# V2.net
KiCad netlist of a schematic drawn in Altium Designer
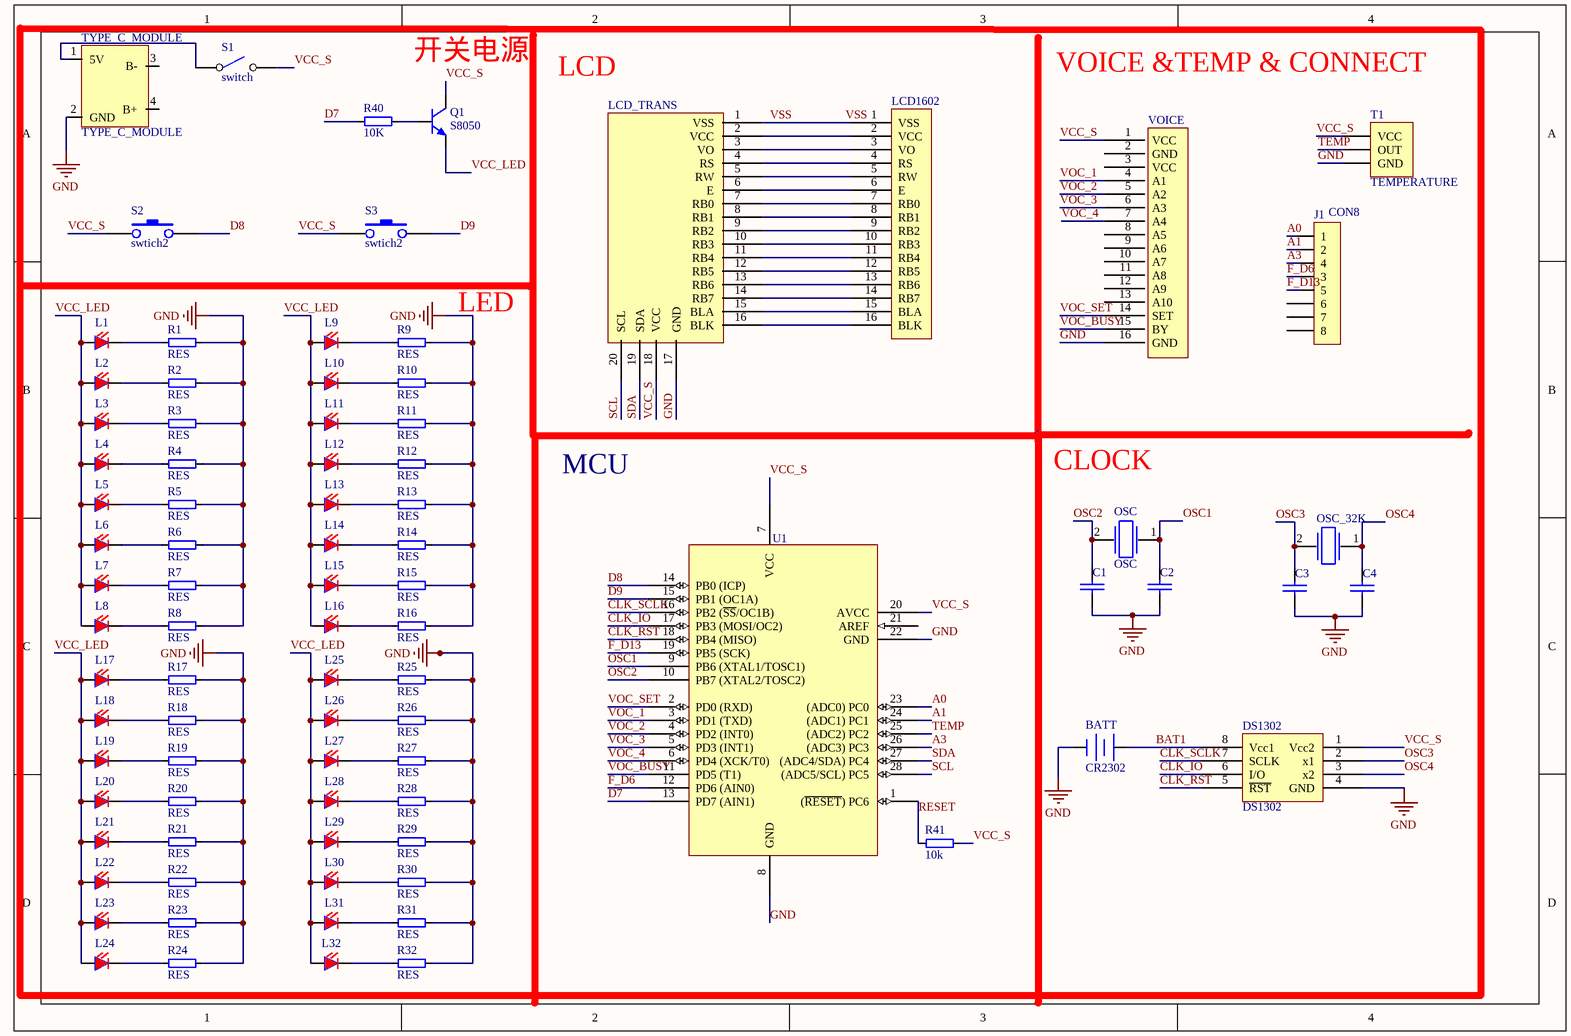
[diagram p0: 生日礼物V2.SchDoc]

(export (version "E")
  (design (tool "Eeschema 10.0.6"))
  (components
    (comp (ref "BATT")
      (value "CR2302")
      (footprint "CR2032_C")
      (description "Multicell Battery")
      (fields (field (name "PUBLISHER") "Altium Limited"))
      (libsource (lib "最小系统") (part "BATTERY"))
    )
    (comp (ref "C1") (value "~") (footprint "CAP") (libsource (lib "最小系统") (part "CAP")))
    (comp (ref "C2") (value "~") (footprint "CAP") (libsource (lib "最小系统") (part "CAP")))
    (comp (ref "C3") (value "~") (footprint "CAP") (libsource (lib "最小系统") (part "CAP")))
    (comp (ref "C4") (value "~") (footprint "CAP") (libsource (lib "最小系统") (part "CAP")))
    (comp (ref "DS1302") (value "DS1302") (footprint "DS1302") (libsource (lib "最小系统") (part "DS1302")))
    (comp (ref "J1") (value "CON8") (footprint "CON8") (libsource (lib "最小系统") (part "CON8")))
    (comp (ref "L1") (value "~") (footprint "LED 5MM-Y") (libsource (lib "最小系统") (part "LED")))
    (comp (ref "L2") (value "~") (footprint "LED 5MM-Y") (libsource (lib "最小系统") (part "LED")))
    (comp (ref "L3") (value "~") (footprint "LED 5MM-Y") (libsource (lib "最小系统") (part "LED")))
    (comp (ref "L4") (value "~") (footprint "LED 5MM-Y") (libsource (lib "最小系统") (part "LED")))
    (comp (ref "L5") (value "~") (footprint "LED 5MM-Y") (libsource (lib "最小系统") (part "LED")))
    (comp (ref "L6") (value "~") (footprint "LED 5MM-Y") (libsource (lib "最小系统") (part "LED")))
    (comp (ref "L7") (value "~") (footprint "LED 5MM-Y") (libsource (lib "最小系统") (part "LED")))
    (comp (ref "L8") (value "~") (footprint "LED 5MM-Y") (libsource (lib "最小系统") (part "LED")))
    (comp (ref "L9") (value "~") (footprint "LED 5MM-Y") (libsource (lib "最小系统") (part "LED")))
    (comp (ref "L10") (value "~") (footprint "LED 5MM-Y") (libsource (lib "最小系统") (part "LED")))
    (comp (ref "L11") (value "~") (footprint "LED 5MM-Y") (libsource (lib "最小系统") (part "LED")))
    (comp (ref "L12") (value "~") (footprint "LED 5MM-Y") (libsource (lib "最小系统") (part "LED")))
    (comp (ref "L13") (value "~") (footprint "LED 5MM-Y") (libsource (lib "最小系统") (part "LED")))
    (comp (ref "L14") (value "~") (footprint "LED 5MM-Y") (libsource (lib "最小系统") (part "LED")))
    (comp (ref "L15") (value "~") (footprint "LED 5MM-Y") (libsource (lib "最小系统") (part "LED")))
    (comp (ref "L16") (value "~") (footprint "LED 5MM-Y") (libsource (lib "最小系统") (part "LED")))
    (comp (ref "L17") (value "~") (footprint "LED 5MM-Y") (libsource (lib "最小系统") (part "LED")))
    (comp (ref "L18") (value "~") (footprint "LED 5MM-Y") (libsource (lib "最小系统") (part "LED")))
    (comp (ref "L19") (value "~") (footprint "LED 5MM-Y") (libsource (lib "最小系统") (part "LED")))
    (comp (ref "L20") (value "~") (footprint "LED 5MM-Y") (libsource (lib "最小系统") (part "LED")))
    (comp (ref "L21") (value "~") (footprint "LED 5MM-Y") (libsource (lib "最小系统") (part "LED")))
    (comp (ref "L22") (value "~") (footprint "LED 5MM-Y") (libsource (lib "最小系统") (part "LED")))
    (comp (ref "L23") (value "~") (footprint "LED 5MM-Y") (libsource (lib "最小系统") (part "LED")))
    (comp (ref "L24") (value "~") (footprint "LED 5MM-Y") (libsource (lib "最小系统") (part "LED")))
    (comp (ref "L25") (value "~") (footprint "LED 5MM-Y") (libsource (lib "最小系统") (part "LED")))
    (comp (ref "L26") (value "~") (footprint "LED 5MM-Y") (libsource (lib "最小系统") (part "LED")))
    (comp (ref "L27") (value "~") (footprint "LED 5MM-Y") (libsource (lib "最小系统") (part "LED")))
    (comp (ref "L28") (value "~") (footprint "LED 5MM-Y") (libsource (lib "最小系统") (part "LED")))
    (comp (ref "L29") (value "~") (footprint "LED 5MM-Y") (libsource (lib "最小系统") (part "LED")))
    (comp (ref "L30") (value "~") (footprint "LED 5MM-Y") (libsource (lib "最小系统") (part "LED")))
    (comp (ref "L31") (value "~") (footprint "LED 5MM-Y") (libsource (lib "最小系统") (part "LED")))
    (comp (ref "L32") (value "~") (footprint "LED 5MM-Y") (libsource (lib "最小系统") (part "LED")))
    (comp (ref "LCD1602") (value "~") (footprint "LCD1602") (libsource (lib "最小系统") (part "LCD1602")))
    (comp (ref "LCD_TRANS") (value "~") (footprint "LCD-TRANS") (libsource (lib "最小系统") (part "LCD_TRANS")))
    (comp (ref "OSC")
      (value "OSC")
      (footprint "OSC HC-49U")
      (description "晶振 32.768KHZ")
      (libsource (lib "最小系统") (part "OSC"))
    )
    (comp (ref "OSC_32K") (value "~") (footprint "osc_32.768K") (libsource (lib "生日礼物V2") (part "OSC_32K")))
    (comp (ref "Q1")
      (value "S8050")
      (footprint "TO92")
      (description "高频放大-NPN型")
      (fields (field (name "版权归属") "源创客"))
      (libsource (lib "最小系统") (part "8050-DIP"))
    )
    (comp (ref "R1") (value "RES") (footprint "0805R") (libsource (lib "最小系统") (part "RES")))
    (comp (ref "R2") (value "RES") (footprint "0805R") (libsource (lib "最小系统") (part "RES")))
    (comp (ref "R3") (value "RES") (footprint "0805R") (libsource (lib "最小系统") (part "RES")))
    (comp (ref "R4") (value "RES") (footprint "0805R") (libsource (lib "最小系统") (part "RES")))
    (comp (ref "R5") (value "RES") (footprint "0805R") (libsource (lib "最小系统") (part "RES")))
    (comp (ref "R6") (value "RES") (footprint "0805R") (libsource (lib "最小系统") (part "RES")))
    (comp (ref "R7") (value "RES") (footprint "0805R") (libsource (lib "最小系统") (part "RES")))
    (comp (ref "R8") (value "RES") (footprint "0805R") (libsource (lib "最小系统") (part "RES")))
    (comp (ref "R9") (value "RES") (footprint "0805R") (libsource (lib "最小系统") (part "RES")))
    (comp (ref "R10") (value "RES") (footprint "0805R") (libsource (lib "最小系统") (part "RES")))
    (comp (ref "R11") (value "RES") (footprint "0805R") (libsource (lib "最小系统") (part "RES")))
    (comp (ref "R12") (value "RES") (footprint "0805R") (libsource (lib "最小系统") (part "RES")))
    (comp (ref "R13") (value "RES") (footprint "0805R") (libsource (lib "最小系统") (part "RES")))
    (comp (ref "R14") (value "RES") (footprint "0805R") (libsource (lib "最小系统") (part "RES")))
    (comp (ref "R15") (value "RES") (footprint "0805R") (libsource (lib "最小系统") (part "RES")))
    (comp (ref "R16") (value "RES") (footprint "0805R") (libsource (lib "最小系统") (part "RES")))
    (comp (ref "R17") (value "RES") (footprint "0805R") (libsource (lib "最小系统") (part "RES")))
    (comp (ref "R18") (value "RES") (footprint "0805R") (libsource (lib "最小系统") (part "RES")))
    (comp (ref "R19") (value "RES") (footprint "0805R") (libsource (lib "最小系统") (part "RES")))
    (comp (ref "R20") (value "RES") (footprint "0805R") (libsource (lib "最小系统") (part "RES")))
    (comp (ref "R21") (value "RES") (footprint "0805R") (libsource (lib "最小系统") (part "RES")))
    (comp (ref "R22") (value "RES") (footprint "0805R") (libsource (lib "最小系统") (part "RES")))
    (comp (ref "R23") (value "RES") (footprint "0805R") (libsource (lib "最小系统") (part "RES")))
    (comp (ref "R24") (value "RES") (footprint "0805R") (libsource (lib "最小系统") (part "RES")))
    (comp (ref "R25") (value "RES") (footprint "0805R") (libsource (lib "最小系统") (part "RES")))
    (comp (ref "R26") (value "RES") (footprint "0805R") (libsource (lib "最小系统") (part "RES")))
    (comp (ref "R27") (value "RES") (footprint "0805R") (libsource (lib "最小系统") (part "RES")))
    (comp (ref "R28") (value "RES") (footprint "0805R") (libsource (lib "最小系统") (part "RES")))
    (comp (ref "R29") (value "RES") (footprint "0805R") (libsource (lib "最小系统") (part "RES")))
    (comp (ref "R30") (value "RES") (footprint "0805R") (libsource (lib "最小系统") (part "RES")))
    (comp (ref "R31") (value "RES") (footprint "0805R") (libsource (lib "最小系统") (part "RES")))
    (comp (ref "R32") (value "RES") (footprint "0805R") (libsource (lib "最小系统") (part "RES")))
    (comp (ref "R40") (value "10K") (footprint "0805R") (libsource (lib "最小系统") (part "RES")))
    (comp (ref "R41") (value "10k") (footprint "0805R") (libsource (lib "最小系统") (part "RES")))
    (comp (ref "S1")
      (value "switch")
      (footprint "switch")
      (description "主开关")
      (libsource (lib "最小系统") (part "switch"))
    )
    (comp (ref "S2")
      (value "swtich2")
      (footprint "switch")
      (description "按钮触发")
      (libsource (lib "最小系统") (part "swtich"))
    )
    (comp (ref "S3") (value "swtich2") (footprint "switch") (libsource (lib "最小系统") (part "swtich")))
    (comp (ref "T1")
      (value "TEMPERATURE")
      (footprint "TEMP_SENSOR")
      (description "温度传感器")
      (libsource (lib "最小系统") (part "TEMPERATURE"))
    )
    (comp (ref "TYPE_C_MODULE")
      (value "TYPE_C_MODULE")
      (footprint "TYPE_C_Module")
      (libsource (lib "最小系统") (part "TYPE_C_MODULE"))
    )
    (comp (ref "U1")
      (value "~")
      (footprint "DIP28")
      (description "Atmel Microcontroller - Library created by carel..  <www.mpfreezone.com>")
      (libsource (lib "最小系统") (part "ATMEGA8_DIP28"))
    )
    (comp (ref "VOICE") (value "~") (footprint "VOICE") (libsource (lib "最小系统") (part "VOICE")))
  )
  (nets
    (net (code "1") (name "/A0") (class "Default")
      (node (ref "J1") (pin "1") (pinfunction "1_1") (pintype "passive"))
      (node (ref "U1") (pin "23") (pinfunction "(ADC0)_PC0_23") (pintype "bidirectional"))
    )
    (net (code "2") (name "/A1") (class "Default")
      (node (ref "J1") (pin "2") (pinfunction "2_2") (pintype "passive"))
      (node (ref "U1") (pin "24") (pinfunction "(ADC1)_PC1_24") (pintype "bidirectional"))
    )
    (net (code "3") (name "/A3") (class "Default")
      (node (ref "J1") (pin "4") (pinfunction "4_4") (pintype "passive"))
      (node (ref "U1") (pin "26") (pinfunction "(ADC3)_PC3_26") (pintype "bidirectional"))
    )
    (net (code "4") (name "/BAT1") (class "Default")
      (node (ref "BATT") (pin "1") (pinfunction "+_1") (pintype "passive"))
      (node (ref "DS1302") (pin "8") (pinfunction "Vcc1_8") (pintype "passive"))
    )
    (net (code "5") (name "/CLK_IO") (class "Default")
      (node (ref "DS1302") (pin "6") (pinfunction "I/O_6") (pintype "passive"))
      (node (ref "U1") (pin "17") (pinfunction "PB3_(MOSI/OC2)_17") (pintype "bidirectional"))
    )
    (net (code "6") (name "/CLK_RST") (class "Default")
      (node (ref "DS1302") (pin "5") (pinfunction "~{RST}_5") (pintype "passive"))
      (node (ref "U1") (pin "18") (pinfunction "PB4_(MISO)_18") (pintype "bidirectional"))
    )
    (net (code "7") (name "/CLK_SCLK") (class "Default")
      (node (ref "DS1302") (pin "7") (pinfunction "SCLK_7") (pintype "passive"))
      (node (ref "U1") (pin "16") (pinfunction "PB2_(~{SS}/OC1B)_16") (pintype "bidirectional"))
    )
    (net (code "8") (name "/D7") (class "Default")
      (node (ref "R40") (pin "1") (pinfunction "1_1") (pintype "passive"))
      (node (ref "U1") (pin "13") (pinfunction "PD7_(AIN1)_13") (pintype "passive"))
    )
    (net (code "9") (name "/D8") (class "Default")
      (node (ref "S2") (pin "2") (pinfunction "2_2") (pintype "passive"))
      (node (ref "U1") (pin "14") (pinfunction "PB0_(ICP)_14") (pintype "bidirectional"))
    )
    (net (code "10") (name "/D9") (class "Default")
      (node (ref "S3") (pin "2") (pinfunction "2_2") (pintype "passive"))
      (node (ref "U1") (pin "15") (pinfunction "PB1_(OC1A)_15") (pintype "bidirectional"))
    )
    (net (code "11") (name "/F_D6") (class "Default")
      (node (ref "J1") (pin "3") (pinfunction "3_3") (pintype "passive"))
      (node (ref "U1") (pin "12") (pinfunction "PD6_(AIN0)_12") (pintype "passive"))
    )
    (net (code "12") (name "/F_D13") (class "Default")
      (node (ref "J1") (pin "5") (pinfunction "5_5") (pintype "passive"))
      (node (ref "U1") (pin "19") (pinfunction "PB5_(SCK)_19") (pintype "bidirectional"))
    )
    (net (code "13") (name "/OSC1") (class "Default")
      (node (ref "C2") (pin "1") (pinfunction "1_1") (pintype "passive"))
      (node (ref "OSC") (pin "1") (pintype "passive"))
      (node (ref "U1") (pin "9") (pinfunction "PB6_(XTAL1/TOSC1)_9") (pintype "passive"))
    )
    (net (code "14") (name "/OSC2") (class "Default")
      (node (ref "C1") (pin "1") (pinfunction "1_1") (pintype "passive"))
      (node (ref "OSC") (pin "2") (pintype "passive"))
      (node (ref "U1") (pin "10") (pinfunction "PB7_(XTAL2/TOSC2)_10") (pintype "passive"))
    )
    (net (code "15") (name "/OSC3") (class "Default")
      (node (ref "C3") (pin "1") (pinfunction "1_1") (pintype "passive"))
      (node (ref "DS1302") (pin "2") (pinfunction "x1_2") (pintype "passive"))
      (node (ref "OSC_32K") (pin "2") (pintype "passive"))
    )
    (net (code "16") (name "/OSC4") (class "Default")
      (node (ref "C4") (pin "1") (pinfunction "1_1") (pintype "passive"))
      (node (ref "DS1302") (pin "3") (pinfunction "x2_3") (pintype "passive"))
      (node (ref "OSC_32K") (pin "1") (pintype "passive"))
    )
    (net (code "17") (name "/RESET") (class "Default")
      (node (ref "R41") (pin "1") (pinfunction "1_1") (pintype "passive"))
      (node (ref "U1") (pin "1") (pinfunction "(~{RESET})_PC6_1") (pintype "bidirectional"))
    )
    (net (code "18") (name "/SCL") (class "Default")
      (node (ref "LCD_TRANS") (pin "20") (pinfunction "SCL_20") (pintype "passive"))
      (node (ref "U1") (pin "28") (pinfunction "(ADC5/SCL)_PC5_28") (pintype "bidirectional"))
    )
    (net (code "19") (name "/SDA") (class "Default")
      (node (ref "LCD_TRANS") (pin "19") (pinfunction "SDA_19") (pintype "passive"))
      (node (ref "U1") (pin "27") (pinfunction "(ADC4/SDA)_PC4_27") (pintype "bidirectional"))
    )
    (net (code "20") (name "/TEMP") (class "Default")
      (node (ref "T1") (pin "2") (pinfunction "OUT_2") (pintype "passive"))
      (node (ref "U1") (pin "25") (pinfunction "(ADC2)_PC2_25") (pintype "bidirectional"))
    )
    (net (code "21") (name "/VCC_LED") (class "Default")
      (node (ref "L1") (pin "1") (pinfunction "A_1") (pintype "passive"))
      (node (ref "L10") (pin "1") (pinfunction "A_1") (pintype "passive"))
      (node (ref "L11") (pin "1") (pinfunction "A_1") (pintype "passive"))
      (node (ref "L12") (pin "1") (pinfunction "A_1") (pintype "passive"))
      (node (ref "L13") (pin "1") (pinfunction "A_1") (pintype "passive"))
      (node (ref "L14") (pin "1") (pinfunction "A_1") (pintype "passive"))
      (node (ref "L15") (pin "1") (pinfunction "A_1") (pintype "passive"))
      (node (ref "L16") (pin "1") (pinfunction "A_1") (pintype "passive"))
      (node (ref "L17") (pin "1") (pinfunction "A_1") (pintype "passive"))
      (node (ref "L18") (pin "1") (pinfunction "A_1") (pintype "passive"))
      (node (ref "L19") (pin "1") (pinfunction "A_1") (pintype "passive"))
      (node (ref "L2") (pin "1") (pinfunction "A_1") (pintype "passive"))
      (node (ref "L20") (pin "1") (pinfunction "A_1") (pintype "passive"))
      (node (ref "L21") (pin "1") (pinfunction "A_1") (pintype "passive"))
      (node (ref "L22") (pin "1") (pinfunction "A_1") (pintype "passive"))
      (node (ref "L23") (pin "1") (pinfunction "A_1") (pintype "passive"))
      (node (ref "L24") (pin "1") (pinfunction "A_1") (pintype "passive"))
      (node (ref "L25") (pin "1") (pinfunction "A_1") (pintype "passive"))
      (node (ref "L26") (pin "1") (pinfunction "A_1") (pintype "passive"))
      (node (ref "L27") (pin "1") (pinfunction "A_1") (pintype "passive"))
      (node (ref "L28") (pin "1") (pinfunction "A_1") (pintype "passive"))
      (node (ref "L29") (pin "1") (pinfunction "A_1") (pintype "passive"))
      (node (ref "L3") (pin "1") (pinfunction "A_1") (pintype "passive"))
      (node (ref "L30") (pin "1") (pinfunction "A_1") (pintype "passive"))
      (node (ref "L31") (pin "1") (pinfunction "A_1") (pintype "passive"))
      (node (ref "L32") (pin "1") (pinfunction "A_1") (pintype "passive"))
      (node (ref "L4") (pin "1") (pinfunction "A_1") (pintype "passive"))
      (node (ref "L5") (pin "1") (pinfunction "A_1") (pintype "passive"))
      (node (ref "L6") (pin "1") (pinfunction "A_1") (pintype "passive"))
      (node (ref "L7") (pin "1") (pinfunction "A_1") (pintype "passive"))
      (node (ref "L8") (pin "1") (pinfunction "A_1") (pintype "passive"))
      (node (ref "L9") (pin "1") (pinfunction "A_1") (pintype "passive"))
      (node (ref "Q1") (pin "1") (pinfunction "E_1") (pintype "passive"))
    )
    (net (code "22") (name "/VCC_S") (class "Default")
      (node (ref "DS1302") (pin "1") (pinfunction "Vcc2_1") (pintype "passive"))
      (node (ref "LCD_TRANS") (pin "18") (pinfunction "VCC_18") (pintype "passive"))
      (node (ref "Q1") (pin "3") (pinfunction "C_3") (pintype "passive"))
      (node (ref "R41") (pin "2") (pinfunction "2_2") (pintype "passive"))
      (node (ref "S1") (pin "2") (pinfunction "2_2") (pintype "passive"))
      (node (ref "S2") (pin "1") (pinfunction "1_1") (pintype "passive"))
      (node (ref "S3") (pin "1") (pinfunction "1_1") (pintype "passive"))
      (node (ref "T1") (pin "1") (pinfunction "VCC_1") (pintype "passive"))
      (node (ref "U1") (pin "20") (pinfunction "AVCC_20") (pintype "passive"))
      (node (ref "U1") (pin "7") (pinfunction "VCC_7") (pintype "passive"))
      (node (ref "VOICE") (pin "1") (pinfunction "VCC_1") (pintype "passive"))
    )
    (net (code "23") (name "/VOC_1") (class "Default")
      (node (ref "U1") (pin "3") (pinfunction "PD1_(TXD)_3") (pintype "bidirectional"))
      (node (ref "VOICE") (pin "4") (pinfunction "A1_4") (pintype "passive"))
    )
    (net (code "24") (name "/VOC_2") (class "Default")
      (node (ref "U1") (pin "4") (pinfunction "PD2_(INT0)_4") (pintype "bidirectional"))
      (node (ref "VOICE") (pin "5") (pinfunction "A2_5") (pintype "passive"))
    )
    (net (code "25") (name "/VOC_3") (class "Default")
      (node (ref "U1") (pin "5") (pinfunction "PD3_(INT1)_5") (pintype "bidirectional"))
      (node (ref "VOICE") (pin "6") (pinfunction "A3_6") (pintype "passive"))
    )
    (net (code "26") (name "/VOC_4") (class "Default")
      (node (ref "U1") (pin "6") (pinfunction "PD4_(XCK/T0)_6") (pintype "bidirectional"))
      (node (ref "VOICE") (pin "7") (pinfunction "A4_7") (pintype "passive"))
    )
    (net (code "27") (name "/VOC_BUSY") (class "Default")
      (node (ref "U1") (pin "11") (pinfunction "PD5_(T1)_11") (pintype "passive"))
      (node (ref "VOICE") (pin "15") (pinfunction "BY_15") (pintype "passive"))
    )
    (net (code "28") (name "/VOC_SET") (class "Default")
      (node (ref "U1") (pin "2") (pinfunction "PD0_(RXD)_2") (pintype "bidirectional"))
      (node (ref "VOICE") (pin "14") (pinfunction "SET_14") (pintype "passive"))
    )
    (net (code "29") (name "/VSS") (class "Default")
      (node (ref "LCD1602") (pin "1") (pinfunction "VSS_1") (pintype "passive"))
      (node (ref "LCD_TRANS") (pin "1") (pinfunction "VSS_1") (pintype "passive"))
    )
    (net (code "30") (name "GND") (class "Default")
      (node (ref "BATT") (pin "2") (pinfunction "-_2") (pintype "passive"))
      (node (ref "C1") (pin "2") (pinfunction "2_2") (pintype "passive"))
      (node (ref "C2") (pin "2") (pinfunction "2_2") (pintype "passive"))
      (node (ref "C3") (pin "2") (pinfunction "2_2") (pintype "passive"))
      (node (ref "C4") (pin "2") (pinfunction "2_2") (pintype "passive"))
      (node (ref "DS1302") (pin "4") (pinfunction "GND_4") (pintype "passive"))
      (node (ref "LCD_TRANS") (pin "17") (pinfunction "GND_17") (pintype "passive"))
      (node (ref "R1") (pin "2") (pinfunction "2_2") (pintype "passive"))
      (node (ref "R10") (pin "2") (pinfunction "2_2") (pintype "passive"))
      (node (ref "R11") (pin "2") (pinfunction "2_2") (pintype "passive"))
      (node (ref "R12") (pin "2") (pinfunction "2_2") (pintype "passive"))
      (node (ref "R13") (pin "2") (pinfunction "2_2") (pintype "passive"))
      (node (ref "R14") (pin "2") (pinfunction "2_2") (pintype "passive"))
      (node (ref "R15") (pin "2") (pinfunction "2_2") (pintype "passive"))
      (node (ref "R16") (pin "2") (pinfunction "2_2") (pintype "passive"))
      (node (ref "R17") (pin "2") (pinfunction "2_2") (pintype "passive"))
      (node (ref "R18") (pin "2") (pinfunction "2_2") (pintype "passive"))
      (node (ref "R19") (pin "2") (pinfunction "2_2") (pintype "passive"))
      (node (ref "R2") (pin "2") (pinfunction "2_2") (pintype "passive"))
      (node (ref "R20") (pin "2") (pinfunction "2_2") (pintype "passive"))
      (node (ref "R21") (pin "2") (pinfunction "2_2") (pintype "passive"))
      (node (ref "R22") (pin "2") (pinfunction "2_2") (pintype "passive"))
      (node (ref "R23") (pin "2") (pinfunction "2_2") (pintype "passive"))
      (node (ref "R24") (pin "2") (pinfunction "2_2") (pintype "passive"))
      (node (ref "R25") (pin "2") (pinfunction "2_2") (pintype "passive"))
      (node (ref "R26") (pin "2") (pinfunction "2_2") (pintype "passive"))
      (node (ref "R27") (pin "2") (pinfunction "2_2") (pintype "passive"))
      (node (ref "R28") (pin "2") (pinfunction "2_2") (pintype "passive"))
      (node (ref "R29") (pin "2") (pinfunction "2_2") (pintype "passive"))
      (node (ref "R3") (pin "2") (pinfunction "2_2") (pintype "passive"))
      (node (ref "R30") (pin "2") (pinfunction "2_2") (pintype "passive"))
      (node (ref "R31") (pin "2") (pinfunction "2_2") (pintype "passive"))
      (node (ref "R32") (pin "2") (pinfunction "2_2") (pintype "passive"))
      (node (ref "R4") (pin "2") (pinfunction "2_2") (pintype "passive"))
      (node (ref "R5") (pin "2") (pinfunction "2_2") (pintype "passive"))
      (node (ref "R6") (pin "2") (pinfunction "2_2") (pintype "passive"))
      (node (ref "R7") (pin "2") (pinfunction "2_2") (pintype "passive"))
      (node (ref "R8") (pin "2") (pinfunction "2_2") (pintype "passive"))
      (node (ref "R9") (pin "2") (pinfunction "2_2") (pintype "passive"))
      (node (ref "T1") (pin "3") (pinfunction "GND_3") (pintype "passive"))
      (node (ref "TYPE_C_MODULE") (pin "2") (pinfunction "GND_2") (pintype "passive"))
      (node (ref "U1") (pin "22") (pinfunction "GND_22") (pintype "passive"))
      (node (ref "U1") (pin "8") (pinfunction "GND_8") (pintype "passive"))
      (node (ref "VOICE") (pin "16") (pinfunction "GND_16") (pintype "passive"))
    )
    (net (code "31") (name "Net-(L1-K)") (class "Default")
      (node (ref "L1") (pin "2") (pinfunction "K_2") (pintype "passive"))
      (node (ref "R1") (pin "1") (pinfunction "1_1") (pintype "passive"))
    )
    (net (code "32") (name "Net-(L2-K)") (class "Default")
      (node (ref "L2") (pin "2") (pinfunction "K_2") (pintype "passive"))
      (node (ref "R2") (pin "1") (pinfunction "1_1") (pintype "passive"))
    )
    (net (code "33") (name "Net-(L3-K)") (class "Default")
      (node (ref "L3") (pin "2") (pinfunction "K_2") (pintype "passive"))
      (node (ref "R3") (pin "1") (pinfunction "1_1") (pintype "passive"))
    )
    (net (code "34") (name "Net-(L4-K)") (class "Default")
      (node (ref "L4") (pin "2") (pinfunction "K_2") (pintype "passive"))
      (node (ref "R4") (pin "1") (pinfunction "1_1") (pintype "passive"))
    )
    (net (code "35") (name "Net-(L5-K)") (class "Default")
      (node (ref "L5") (pin "2") (pinfunction "K_2") (pintype "passive"))
      (node (ref "R5") (pin "1") (pinfunction "1_1") (pintype "passive"))
    )
    (net (code "36") (name "Net-(L6-K)") (class "Default")
      (node (ref "L6") (pin "2") (pinfunction "K_2") (pintype "passive"))
      (node (ref "R6") (pin "1") (pinfunction "1_1") (pintype "passive"))
    )
    (net (code "37") (name "Net-(L7-K)") (class "Default")
      (node (ref "L7") (pin "2") (pinfunction "K_2") (pintype "passive"))
      (node (ref "R7") (pin "1") (pinfunction "1_1") (pintype "passive"))
    )
    (net (code "38") (name "Net-(L8-K)") (class "Default")
      (node (ref "L8") (pin "2") (pinfunction "K_2") (pintype "passive"))
      (node (ref "R8") (pin "1") (pinfunction "1_1") (pintype "passive"))
    )
    (net (code "39") (name "Net-(L9-K)") (class "Default")
      (node (ref "L9") (pin "2") (pinfunction "K_2") (pintype "passive"))
      (node (ref "R9") (pin "1") (pinfunction "1_1") (pintype "passive"))
    )
    (net (code "40") (name "Net-(L10-K)") (class "Default")
      (node (ref "L10") (pin "2") (pinfunction "K_2") (pintype "passive"))
      (node (ref "R10") (pin "1") (pinfunction "1_1") (pintype "passive"))
    )
    (net (code "41") (name "Net-(L11-K)") (class "Default")
      (node (ref "L11") (pin "2") (pinfunction "K_2") (pintype "passive"))
      (node (ref "R11") (pin "1") (pinfunction "1_1") (pintype "passive"))
    )
    (net (code "42") (name "Net-(L12-K)") (class "Default")
      (node (ref "L12") (pin "2") (pinfunction "K_2") (pintype "passive"))
      (node (ref "R12") (pin "1") (pinfunction "1_1") (pintype "passive"))
    )
    (net (code "43") (name "Net-(L13-K)") (class "Default")
      (node (ref "L13") (pin "2") (pinfunction "K_2") (pintype "passive"))
      (node (ref "R13") (pin "1") (pinfunction "1_1") (pintype "passive"))
    )
    (net (code "44") (name "Net-(L14-K)") (class "Default")
      (node (ref "L14") (pin "2") (pinfunction "K_2") (pintype "passive"))
      (node (ref "R14") (pin "1") (pinfunction "1_1") (pintype "passive"))
    )
    (net (code "45") (name "Net-(L15-K)") (class "Default")
      (node (ref "L15") (pin "2") (pinfunction "K_2") (pintype "passive"))
      (node (ref "R15") (pin "1") (pinfunction "1_1") (pintype "passive"))
    )
    (net (code "46") (name "Net-(L16-K)") (class "Default")
      (node (ref "L16") (pin "2") (pinfunction "K_2") (pintype "passive"))
      (node (ref "R16") (pin "1") (pinfunction "1_1") (pintype "passive"))
    )
    (net (code "47") (name "Net-(L17-K)") (class "Default")
      (node (ref "L17") (pin "2") (pinfunction "K_2") (pintype "passive"))
      (node (ref "R17") (pin "1") (pinfunction "1_1") (pintype "passive"))
    )
    (net (code "48") (name "Net-(L18-K)") (class "Default")
      (node (ref "L18") (pin "2") (pinfunction "K_2") (pintype "passive"))
      (node (ref "R18") (pin "1") (pinfunction "1_1") (pintype "passive"))
    )
    (net (code "49") (name "Net-(L19-K)") (class "Default")
      (node (ref "L19") (pin "2") (pinfunction "K_2") (pintype "passive"))
      (node (ref "R19") (pin "1") (pinfunction "1_1") (pintype "passive"))
    )
    (net (code "50") (name "Net-(L20-K)") (class "Default")
      (node (ref "L20") (pin "2") (pinfunction "K_2") (pintype "passive"))
      (node (ref "R20") (pin "1") (pinfunction "1_1") (pintype "passive"))
    )
    (net (code "51") (name "Net-(L21-K)") (class "Default")
      (node (ref "L21") (pin "2") (pinfunction "K_2") (pintype "passive"))
      (node (ref "R21") (pin "1") (pinfunction "1_1") (pintype "passive"))
    )
    (net (code "52") (name "Net-(L22-K)") (class "Default")
      (node (ref "L22") (pin "2") (pinfunction "K_2") (pintype "passive"))
      (node (ref "R22") (pin "1") (pinfunction "1_1") (pintype "passive"))
    )
    (net (code "53") (name "Net-(L23-K)") (class "Default")
      (node (ref "L23") (pin "2") (pinfunction "K_2") (pintype "passive"))
      (node (ref "R23") (pin "1") (pinfunction "1_1") (pintype "passive"))
    )
    (net (code "54") (name "Net-(L24-K)") (class "Default")
      (node (ref "L24") (pin "2") (pinfunction "K_2") (pintype "passive"))
      (node (ref "R24") (pin "1") (pinfunction "1_1") (pintype "passive"))
    )
    (net (code "55") (name "Net-(L25-K)") (class "Default")
      (node (ref "L25") (pin "2") (pinfunction "K_2") (pintype "passive"))
      (node (ref "R25") (pin "1") (pinfunction "1_1") (pintype "passive"))
    )
    (net (code "56") (name "Net-(L26-K)") (class "Default")
      (node (ref "L26") (pin "2") (pinfunction "K_2") (pintype "passive"))
      (node (ref "R26") (pin "1") (pinfunction "1_1") (pintype "passive"))
    )
    (net (code "57") (name "Net-(L27-K)") (class "Default")
      (node (ref "L27") (pin "2") (pinfunction "K_2") (pintype "passive"))
      (node (ref "R27") (pin "1") (pinfunction "1_1") (pintype "passive"))
    )
    (net (code "58") (name "Net-(L28-K)") (class "Default")
      (node (ref "L28") (pin "2") (pinfunction "K_2") (pintype "passive"))
      (node (ref "R28") (pin "1") (pinfunction "1_1") (pintype "passive"))
    )
    (net (code "59") (name "Net-(L29-K)") (class "Default")
      (node (ref "L29") (pin "2") (pinfunction "K_2") (pintype "passive"))
      (node (ref "R29") (pin "1") (pinfunction "1_1") (pintype "passive"))
    )
    (net (code "60") (name "Net-(L30-K)") (class "Default")
      (node (ref "L30") (pin "2") (pinfunction "K_2") (pintype "passive"))
      (node (ref "R30") (pin "1") (pinfunction "1_1") (pintype "passive"))
    )
    (net (code "61") (name "Net-(L31-K)") (class "Default")
      (node (ref "L31") (pin "2") (pinfunction "K_2") (pintype "passive"))
      (node (ref "R31") (pin "1") (pinfunction "1_1") (pintype "passive"))
    )
    (net (code "62") (name "Net-(L32-K)") (class "Default")
      (node (ref "L32") (pin "2") (pinfunction "K_2") (pintype "passive"))
      (node (ref "R32") (pin "1") (pinfunction "1_1") (pintype "passive"))
    )
    (net (code "63") (name "Net-(LCD1602-BLA)") (class "Default")
      (node (ref "LCD1602") (pin "15") (pinfunction "BLA_15") (pintype "passive"))
      (node (ref "LCD_TRANS") (pin "15") (pinfunction "BLA_15") (pintype "passive"))
    )
    (net (code "64") (name "Net-(LCD1602-BLK)") (class "Default")
      (node (ref "LCD1602") (pin "16") (pinfunction "BLK_16") (pintype "passive"))
      (node (ref "LCD_TRANS") (pin "16") (pinfunction "BLK_16") (pintype "passive"))
    )
    (net (code "65") (name "Net-(LCD1602-E)") (class "Default")
      (node (ref "LCD1602") (pin "6") (pinfunction "E_6") (pintype "passive"))
      (node (ref "LCD_TRANS") (pin "6") (pinfunction "E_6") (pintype "passive"))
    )
    (net (code "66") (name "Net-(LCD1602-RB0)") (class "Default")
      (node (ref "LCD1602") (pin "7") (pinfunction "RB0_7") (pintype "passive"))
      (node (ref "LCD_TRANS") (pin "7") (pinfunction "RB0_7") (pintype "passive"))
    )
    (net (code "67") (name "Net-(LCD1602-RB1)") (class "Default")
      (node (ref "LCD1602") (pin "8") (pinfunction "RB1_8") (pintype "passive"))
      (node (ref "LCD_TRANS") (pin "8") (pinfunction "RB1_8") (pintype "passive"))
    )
    (net (code "68") (name "Net-(LCD1602-RB2)") (class "Default")
      (node (ref "LCD1602") (pin "9") (pinfunction "RB2_9") (pintype "passive"))
      (node (ref "LCD_TRANS") (pin "9") (pinfunction "RB2_9") (pintype "passive"))
    )
    (net (code "69") (name "Net-(LCD1602-RB3)") (class "Default")
      (node (ref "LCD1602") (pin "10") (pinfunction "RB3_10") (pintype "passive"))
      (node (ref "LCD_TRANS") (pin "10") (pinfunction "RB3_10") (pintype "passive"))
    )
    (net (code "70") (name "Net-(LCD1602-RB4)") (class "Default")
      (node (ref "LCD1602") (pin "11") (pinfunction "RB4_11") (pintype "passive"))
      (node (ref "LCD_TRANS") (pin "11") (pinfunction "RB4_11") (pintype "passive"))
    )
    (net (code "71") (name "Net-(LCD1602-RB5)") (class "Default")
      (node (ref "LCD1602") (pin "12") (pinfunction "RB5_12") (pintype "passive"))
      (node (ref "LCD_TRANS") (pin "12") (pinfunction "RB5_12") (pintype "passive"))
    )
    (net (code "72") (name "Net-(LCD1602-RB6)") (class "Default")
      (node (ref "LCD1602") (pin "13") (pinfunction "RB6_13") (pintype "passive"))
      (node (ref "LCD_TRANS") (pin "13") (pinfunction "RB6_13") (pintype "passive"))
    )
    (net (code "73") (name "Net-(LCD1602-RB7)") (class "Default")
      (node (ref "LCD1602") (pin "14") (pinfunction "RB7_14") (pintype "passive"))
      (node (ref "LCD_TRANS") (pin "14") (pinfunction "RB7_14") (pintype "passive"))
    )
    (net (code "74") (name "Net-(LCD1602-RS)") (class "Default")
      (node (ref "LCD1602") (pin "4") (pinfunction "RS_4") (pintype "passive"))
      (node (ref "LCD_TRANS") (pin "4") (pinfunction "RS_4") (pintype "passive"))
    )
    (net (code "75") (name "Net-(LCD1602-RW)") (class "Default")
      (node (ref "LCD1602") (pin "5") (pinfunction "RW_5") (pintype "passive"))
      (node (ref "LCD_TRANS") (pin "5") (pinfunction "RW_5") (pintype "passive"))
    )
    (net (code "76") (name "Net-(LCD1602-VCC)") (class "Default")
      (node (ref "LCD1602") (pin "2") (pinfunction "VCC_2") (pintype "passive"))
      (node (ref "LCD_TRANS") (pin "2") (pinfunction "VCC_2") (pintype "passive"))
    )
    (net (code "77") (name "Net-(LCD1602-VO)") (class "Default")
      (node (ref "LCD1602") (pin "3") (pinfunction "VO_3") (pintype "passive"))
      (node (ref "LCD_TRANS") (pin "3") (pinfunction "VO_3") (pintype "passive"))
    )
    (net (code "78") (name "Net-(Q1-B)") (class "Default")
      (node (ref "Q1") (pin "2") (pinfunction "B_2") (pintype "passive"))
      (node (ref "R40") (pin "2") (pinfunction "2_2") (pintype "passive"))
    )
    (net (code "79") (name "Net-(TYPE_C_MODULE-5V)") (class "Default")
      (node (ref "S1") (pin "1") (pinfunction "1_1") (pintype "passive"))
      (node (ref "TYPE_C_MODULE") (pin "1") (pinfunction "5V_1") (pintype "passive"))
    )
    (net (code "80") (name "unconnected-(J1-Pad6)") (class "Default")
      (node (ref "J1") (pin "6") (pinfunction "6_6") (pintype "passive"))
    )
    (net (code "81") (name "unconnected-(J1-Pad7)") (class "Default")
      (node (ref "J1") (pin "7") (pinfunction "7_7") (pintype "passive"))
    )
    (net (code "82") (name "unconnected-(J1-Pad8)") (class "Default")
      (node (ref "J1") (pin "8") (pinfunction "8_8") (pintype "passive"))
    )
    (net (code "83") (name "unconnected-(TYPE_C_MODULE-B+-Pad4)") (class "Default")
      (node (ref "TYPE_C_MODULE") (pin "4") (pinfunction "B+_4") (pintype "passive"))
    )
    (net (code "84") (name "unconnected-(TYPE_C_MODULE-B--Pad3)") (class "Default")
      (node (ref "TYPE_C_MODULE") (pin "3") (pinfunction "B-_3") (pintype "passive"))
    )
    (net (code "85") (name "unconnected-(U1-AREF-Pad21)") (class "Default")
      (node (ref "U1") (pin "21") (pinfunction "AREF_21") (pintype "input"))
    )
    (net (code "86") (name "unconnected-(VOICE-A5-Pad8)") (class "Default")
      (node (ref "VOICE") (pin "8") (pinfunction "A5_8") (pintype "passive"))
    )
    (net (code "87") (name "unconnected-(VOICE-A6-Pad9)") (class "Default")
      (node (ref "VOICE") (pin "9") (pinfunction "A6_9") (pintype "passive"))
    )
    (net (code "88") (name "unconnected-(VOICE-A7-Pad10)") (class "Default")
      (node (ref "VOICE") (pin "10") (pinfunction "A7_10") (pintype "passive"))
    )
    (net (code "89") (name "unconnected-(VOICE-A8-Pad11)") (class "Default")
      (node (ref "VOICE") (pin "11") (pinfunction "A8_11") (pintype "passive"))
    )
    (net (code "90") (name "unconnected-(VOICE-A9-Pad12)") (class "Default")
      (node (ref "VOICE") (pin "12") (pinfunction "A9_12") (pintype "passive"))
    )
    (net (code "91") (name "unconnected-(VOICE-A10-Pad13)") (class "Default")
      (node (ref "VOICE") (pin "13") (pinfunction "A10_13") (pintype "passive"))
    )
    (net (code "92") (name "unconnected-(VOICE-GND-Pad2)") (class "Default")
      (node (ref "VOICE") (pin "2") (pinfunction "GND_2") (pintype "passive"))
    )
    (net (code "93") (name "unconnected-(VOICE-VCC-Pad3)") (class "Default")
      (node (ref "VOICE") (pin "3") (pinfunction "VCC_3") (pintype "passive"))
    )
  )
)
